# ProPrj_DCDC_LDO__2025-04-18.net
KiCad netlist of a schematic drawn in EasyEDA Pro
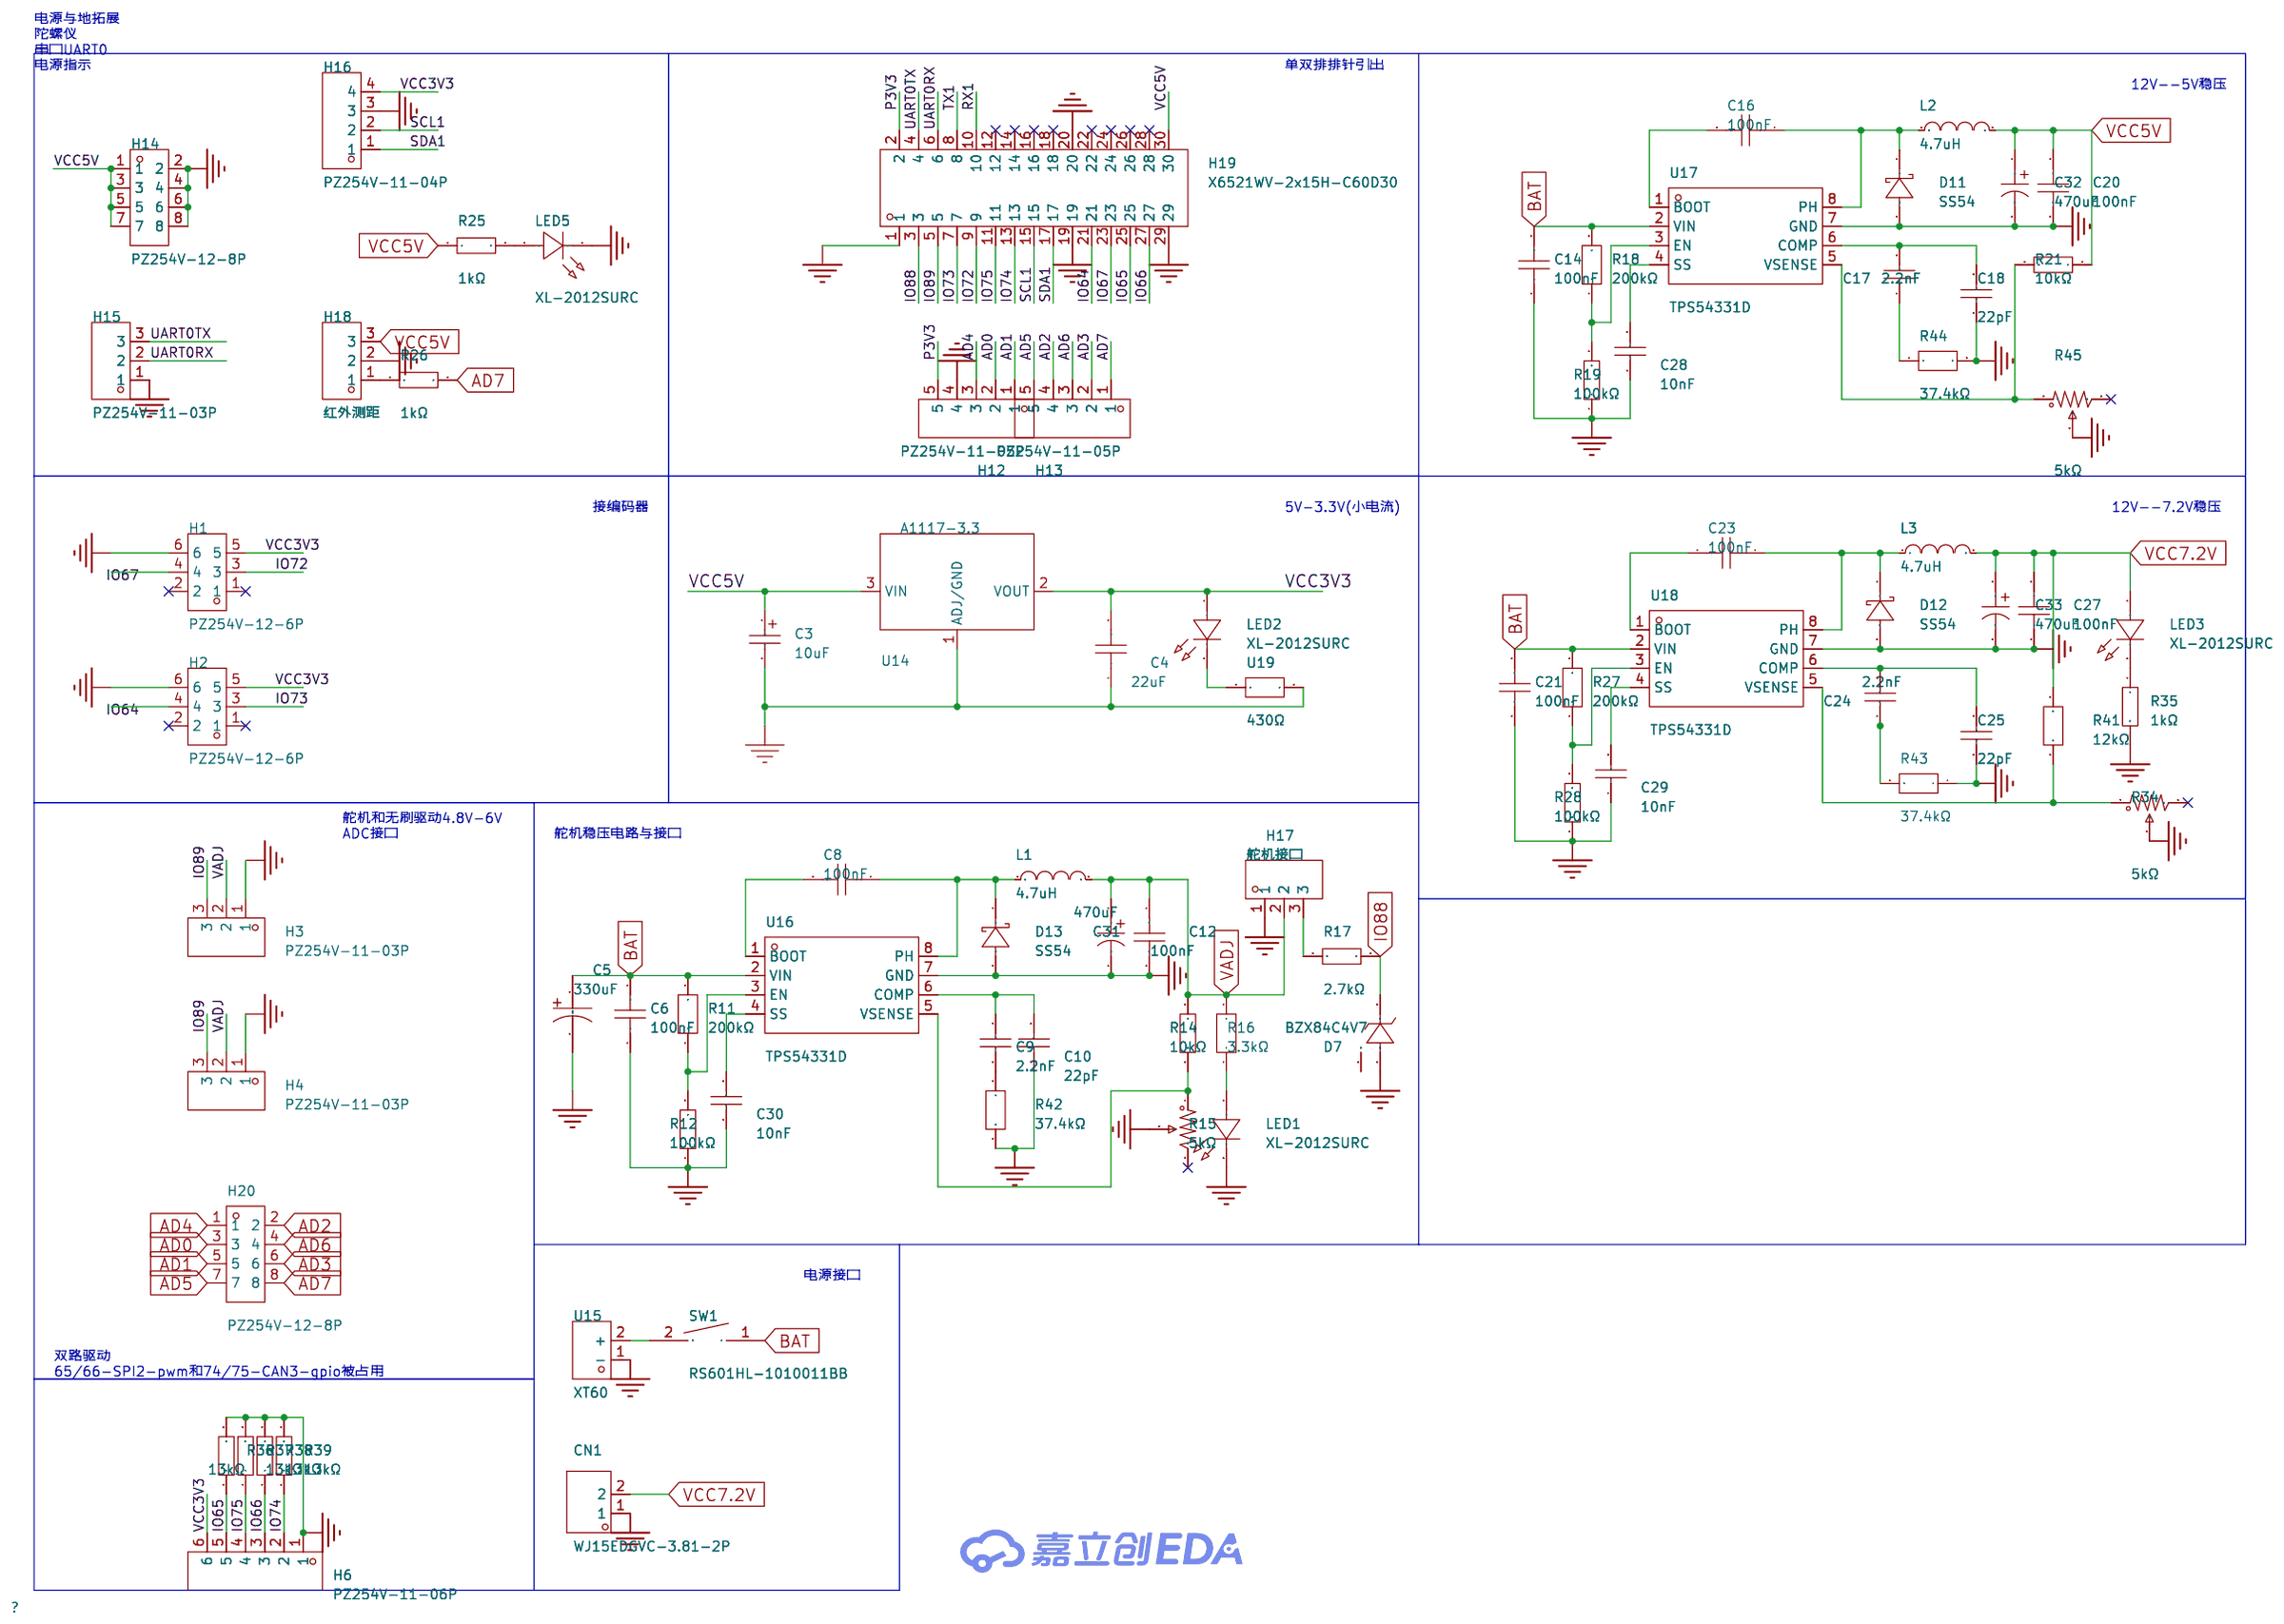
[diagram p0: schematic sheet]

(export (version "E")
  (design (tool "Eeschema 10.0.6"))
  (components
    (comp (ref "C3")
      (value "10uF")
      (footprint "easyedapro:CAP-SMD_L6.0-W3.2")
      (description "容值:10uF;精度:±10%;额定电压:16V;等效串联电阻:2Ω@100kHz;")
      (fields (field (name "Manufacturer Part") "TAJC106K016RNJ") (field (name "Manufacturer") "Kyocera AVX"))
      (libsource (lib "easyedapro") (part "TAJC106K016RNJ"))
    )
    (comp (ref "C4")
      (value "22uF")
      (footprint "easyedapro:C0805")
      (description "容值:22uF;精度:±20%;额定电压:35V;材质(温度系数):X5R;")
      (fields
        (field (name "Manufacturer Part") "CGA0805X5R226M350MT")
        (field (name "Manufacturer") "HRE(芯声)")
      )
      (libsource (lib "easyedapro") (part "CGA0805X5R226M350MT"))
    )
    (comp (ref "C5")
      (value "330uF")
      (footprint "easyedapro:CAP-SMD_BD8.0-L8.3-W8.3-LS9.3-FD-1")
      (description "容值:330uF;精度:±20%;额定电压:25V;纹波电流:228mA@120Hz;等效串联电阻(ESR):-;")
      (fields (field (name "Manufacturer Part") "RVT1E331M0810") (field (name "Manufacturer") "ROQANG(容强)"))
      (libsource (lib "easyedapro") (part "RVT1E331M0810_C335985"))
    )
    (comp (ref "C6")
      (value "100nF")
      (footprint "easyedapro:C0805")
      (description "容值:100nF;精度:±10%;额定电压:50V;材质(温度系数):X7R;")
      (fields
        (field (name "Manufacturer Part") "CC0805KRX7R9BB104")
        (field (name "Manufacturer") "YAGEO(国巨)")
      )
      (libsource (lib "easyedapro") (part "CC0805KRX7R9BB104"))
    )
    (comp (ref "C8")
      (value "100nF")
      (footprint "easyedapro:C0805")
      (description "容值:100nF;精度:±10%;额定电压:50V;材质(温度系数):X7R;")
      (fields
        (field (name "Manufacturer Part") "CC0805KRX7R9BB104")
        (field (name "Manufacturer") "YAGEO(国巨)")
      )
      (libsource (lib "easyedapro") (part "CC0805KRX7R9BB104"))
    )
    (comp (ref "C9")
      (value "2.2nF")
      (footprint "easyedapro:C0805")
      (description "容值:2.2nF;精度:±5%;额定电压:50V;材质(温度系数):C0G;")
      (fields
        (field (name "Manufacturer Part") "CL21C222JBFNNNE")
        (field (name "Manufacturer") "SAMSUNG(三星)")
      )
      (libsource (lib "easyedapro") (part "CL21C222JBFNNNE"))
    )
    (comp (ref "C10")
      (value "22pF")
      (footprint "easyedapro:C0603")
      (description "容值:22pF;精度:±5%;额定电压:50V;材质(温度系数):NP0;")
      (fields
        (field (name "Manufacturer Part") "CC0603JRNPO9BN220")
        (field (name "Manufacturer") "YAGEO(国巨)")
      )
      (libsource (lib "easyedapro") (part "CC0603JRNPO9BN220"))
    )
    (comp (ref "C12")
      (value "100nF")
      (footprint "easyedapro:C0805")
      (description "容值:100nF;精度:±10%;额定电压:50V;材质(温度系数):X7R;")
      (fields
        (field (name "Manufacturer Part") "CC0805KRX7R9BB104")
        (field (name "Manufacturer") "YAGEO(国巨)")
      )
      (libsource (lib "easyedapro") (part "CC0805KRX7R9BB104"))
    )
    (comp (ref "C14")
      (value "100nF")
      (footprint "easyedapro:C0805")
      (description "容值:100nF;精度:±10%;额定电压:50V;材质(温度系数):X7R;")
      (fields
        (field (name "Manufacturer Part") "CC0805KRX7R9BB104")
        (field (name "Manufacturer") "YAGEO(国巨)")
      )
      (libsource (lib "easyedapro") (part "CC0805KRX7R9BB104"))
    )
    (comp (ref "C16")
      (value "100nF")
      (footprint "easyedapro:C0805")
      (description "容值:100nF;精度:±10%;额定电压:50V;材质(温度系数):X7R;")
      (fields
        (field (name "Manufacturer Part") "CC0805KRX7R9BB104")
        (field (name "Manufacturer") "YAGEO(国巨)")
      )
      (libsource (lib "easyedapro") (part "CC0805KRX7R9BB104"))
    )
    (comp (ref "C17")
      (value "2.2nF")
      (footprint "easyedapro:C0805")
      (description "容值:2.2nF;精度:±5%;额定电压:50V;材质(温度系数):C0G;")
      (fields
        (field (name "Manufacturer Part") "CL21C222JBFNNNE")
        (field (name "Manufacturer") "SAMSUNG(三星)")
      )
      (libsource (lib "easyedapro") (part "CL21C222JBFNNNE"))
    )
    (comp (ref "C18")
      (value "22pF")
      (footprint "easyedapro:C0603")
      (description "容值:22pF;精度:±5%;额定电压:50V;材质(温度系数):NP0;")
      (fields
        (field (name "Manufacturer Part") "CC0603JRNPO9BN220")
        (field (name "Manufacturer") "YAGEO(国巨)")
      )
      (libsource (lib "easyedapro") (part "CC0603JRNPO9BN220"))
    )
    (comp (ref "C20")
      (value "100nF")
      (footprint "easyedapro:C0805")
      (description "容值:100nF;精度:±10%;额定电压:50V;材质(温度系数):X7R;")
      (fields
        (field (name "Manufacturer Part") "CC0805KRX7R9BB104")
        (field (name "Manufacturer") "YAGEO(国巨)")
      )
      (libsource (lib "easyedapro") (part "CC0805KRX7R9BB104"))
    )
    (comp (ref "C21")
      (value "100nF")
      (footprint "easyedapro:C0805")
      (description "容值:100nF;精度:±10%;额定电压:50V;材质(温度系数):X7R;")
      (fields
        (field (name "Manufacturer Part") "CC0805KRX7R9BB104")
        (field (name "Manufacturer") "YAGEO(国巨)")
      )
      (libsource (lib "easyedapro") (part "CC0805KRX7R9BB104"))
    )
    (comp (ref "C23")
      (value "100nF")
      (footprint "easyedapro:C0805")
      (description "容值:100nF;精度:±10%;额定电压:50V;材质(温度系数):X7R;")
      (fields
        (field (name "Manufacturer Part") "CC0805KRX7R9BB104")
        (field (name "Manufacturer") "YAGEO(国巨)")
      )
      (libsource (lib "easyedapro") (part "CC0805KRX7R9BB104"))
    )
    (comp (ref "C24")
      (value "2.2nF")
      (footprint "easyedapro:C0805")
      (description "容值:2.2nF;精度:±5%;额定电压:50V;材质(温度系数):C0G;")
      (fields
        (field (name "Manufacturer Part") "CL21C222JBFNNNE")
        (field (name "Manufacturer") "SAMSUNG(三星)")
      )
      (libsource (lib "easyedapro") (part "CL21C222JBFNNNE"))
    )
    (comp (ref "C25")
      (value "22pF")
      (footprint "easyedapro:C0603")
      (description "容值:22pF;精度:±5%;额定电压:50V;材质(温度系数):NP0;")
      (fields
        (field (name "Manufacturer Part") "CC0603JRNPO9BN220")
        (field (name "Manufacturer") "YAGEO(国巨)")
      )
      (libsource (lib "easyedapro") (part "CC0603JRNPO9BN220"))
    )
    (comp (ref "C27")
      (value "100nF")
      (footprint "easyedapro:C0805")
      (description "容值:100nF;精度:±10%;额定电压:50V;材质(温度系数):X7R;")
      (fields
        (field (name "Manufacturer Part") "CC0805KRX7R9BB104")
        (field (name "Manufacturer") "YAGEO(国巨)")
      )
      (libsource (lib "easyedapro") (part "CC0805KRX7R9BB104"))
    )
    (comp (ref "C28")
      (value "10nF")
      (footprint "easyedapro:C0805")
      (description "容值:10nF;精度:±10%;额定电压:50V;材质(温度系数):X7R;")
      (fields
        (field (name "Manufacturer Part") "CL21B103KBANNNC")
        (field (name "Manufacturer") "SAMSUNG(三星)")
      )
      (libsource (lib "easyedapro") (part "CL21B103KBANNNC"))
    )
    (comp (ref "C29")
      (value "10nF")
      (footprint "easyedapro:C0805")
      (description "容值:10nF;精度:±10%;额定电压:50V;材质(温度系数):X7R;")
      (fields
        (field (name "Manufacturer Part") "CL21B103KBANNNC")
        (field (name "Manufacturer") "SAMSUNG(三星)")
      )
      (libsource (lib "easyedapro") (part "CL21B103KBANNNC"))
    )
    (comp (ref "C30")
      (value "10nF")
      (footprint "easyedapro:C0805")
      (description "容值:10nF;精度:±10%;额定电压:50V;材质(温度系数):X7R;")
      (fields
        (field (name "Manufacturer Part") "CL21B103KBANNNC")
        (field (name "Manufacturer") "SAMSUNG(三星)")
      )
      (libsource (lib "easyedapro") (part "CL21B103KBANNNC"))
    )
    (comp (ref "C31")
      (value "470uF")
      (footprint "easyedapro:CAP-SMD_BD8.0-L8.3-W8.3-LS8.9-FD")
      (description "容值:470uF;精度:±20%;额定电压:16V;纹波电流:240mA@120Hz;")
      (fields (field (name "Manufacturer Part") "CK1C471M-CRF10") (field (name "Manufacturer") "ROQANG(容强)"))
      (libsource (lib "easyedapro") (part "CK1C471M-CRF10_C5162359"))
    )
    (comp (ref "C32")
      (value "470uF")
      (footprint "easyedapro:CAP-SMD_BD8.0-L8.3-W8.3-LS8.9-FD")
      (description "容值:470uF;精度:±20%;额定电压:16V;纹波电流:240mA@120Hz;")
      (fields (field (name "Manufacturer Part") "CK1C471M-CRF10") (field (name "Manufacturer") "ROQANG(容强)"))
      (libsource (lib "easyedapro") (part "CK1C471M-CRF10_C5162359"))
    )
    (comp (ref "C33")
      (value "470uF")
      (footprint "easyedapro:CAP-SMD_BD8.0-L8.3-W8.3-LS8.9-FD")
      (description "容值:470uF;精度:±20%;额定电压:16V;纹波电流:240mA@120Hz;")
      (fields (field (name "Manufacturer Part") "CK1C471M-CRF10") (field (name "Manufacturer") "ROQANG(容强)"))
      (libsource (lib "easyedapro") (part "CK1C471M-CRF10_C5162359"))
    )
    (comp (ref "CN1")
      (value "WJ15EDGVC-3.81-2P")
      (footprint "easyedapro:CONN-TH_WJ15EDGVC-3.81-2P")
      (fields (field (name "Manufacturer") "KANGNEX(康奈克斯电气)"))
      (libsource (lib "easyedapro") (part "WJ15EDGVC-3.81-2P"))
    )
    (comp (ref "D7")
      (value "BZX84C4V7")
      (footprint "easyedapro:SOT-23-3_L2.9-W1.3-P1.90-LS2.4-BR")
      (description "二极管配置:独立式;稳压值(标称值):4.7V;稳压值(范围):4.4V~5V;耗散功率(Pd):350mW;")
      (fields (field (name "Manufacturer") "LGE(鲁光)"))
      (libsource (lib "easyedapro") (part "BZX84C4V7_C841158"))
    )
    (comp (ref "D11")
      (value "SS54")
      (footprint "easyedapro:SMA_L4.3-W2.6-LS5.0-RD")
      (description "二极管配置:独立式;正向压降(Vf):550mV@5A;直流反向耐压(Vr):40V;整流电流:5A;")
      (fields (field (name "Manufacturer") "TWGMC(台湾迪嘉)"))
      (libsource (lib "easyedapro") (part "SS54_C727065"))
    )
    (comp (ref "D12")
      (value "SS54")
      (footprint "easyedapro:SMA_L4.3-W2.6-LS5.0-RD")
      (description "二极管配置:独立式;正向压降(Vf):550mV@5A;直流反向耐压(Vr):40V;整流电流:5A;")
      (fields (field (name "Manufacturer") "TWGMC(台湾迪嘉)"))
      (libsource (lib "easyedapro") (part "SS54_C727065"))
    )
    (comp (ref "D13")
      (value "SS54")
      (footprint "easyedapro:SMA_L4.3-W2.6-LS5.0-RD")
      (description "二极管配置:独立式;正向压降(Vf):550mV@5A;直流反向耐压(Vr):40V;整流电流:5A;")
      (fields (field (name "Manufacturer") "TWGMC(台湾迪嘉)"))
      (libsource (lib "easyedapro") (part "SS54_C727065"))
    )
    (comp (ref "H1")
      (value "PZ254V-12-6P")
      (footprint "easyedapro:HDR-TH_6P-P2.54-V-M-R2-C3-S2.54")
      (fields (field (name "Manufacturer") "XFCN(兴飞)"))
      (libsource (lib "easyedapro") (part "PZ254V-12-6P"))
    )
    (comp (ref "H2")
      (value "PZ254V-12-6P")
      (footprint "easyedapro:HDR-TH_6P-P2.54-V-M-R2-C3-S2.54")
      (fields (field (name "Manufacturer") "XFCN(兴飞)"))
      (libsource (lib "easyedapro") (part "PZ254V-12-6P"))
    )
    (comp (ref "H3")
      (value "PZ254V-11-03P")
      (footprint "easyedapro:HDR-TH_3P-P2.54-V-M")
      (fields (field (name "Manufacturer") "XFCN(兴飞)"))
      (libsource (lib "easyedapro") (part "PZ254V-11-03P_C2937625"))
    )
    (comp (ref "H4")
      (value "PZ254V-11-03P")
      (footprint "easyedapro:HDR-TH_3P-P2.54-V-M")
      (fields (field (name "Manufacturer") "XFCN(兴飞)"))
      (libsource (lib "easyedapro") (part "PZ254V-11-03P_C2937625"))
    )
    (comp (ref "H6")
      (value "PZ254V-11-06P")
      (footprint "easyedapro:HDR-TH_6P-P2.54-V-M")
      (fields (field (name "Manufacturer") "XFCN(兴飞)"))
      (libsource (lib "easyedapro") (part "PZ254V-11-06P"))
    )
    (comp (ref "H12")
      (value "PZ254V-11-05P")
      (footprint "easyedapro:HDR-TH_5P-P2.54-V-M")
      (fields (field (name "Manufacturer") "XFCN(兴飞)"))
      (libsource (lib "easyedapro") (part "PZ254V-11-05P"))
    )
    (comp (ref "H13")
      (value "PZ254V-11-05P")
      (footprint "easyedapro:HDR-TH_5P-P2.54-V-M")
      (fields (field (name "Manufacturer") "XFCN(兴飞)"))
      (libsource (lib "easyedapro") (part "PZ254V-11-05P"))
    )
    (comp (ref "H14")
      (value "PZ254V-12-8P")
      (footprint "easyedapro:HDR-TH_8P-P2.54-V-M-R2-C4-S2.54")
      (fields (field (name "Manufacturer") "XFCN(兴飞)"))
      (libsource (lib "easyedapro") (part "PZ254V-12-8P"))
    )
    (comp (ref "H15")
      (value "PZ254V-11-03P")
      (footprint "easyedapro:HDR-TH_3P-P2.54-V-M")
      (fields (field (name "Manufacturer") "XFCN(兴飞)"))
      (libsource (lib "easyedapro") (part "PZ254V-11-03P_C2937625"))
    )
    (comp (ref "H16")
      (value "PZ254V-11-04P")
      (footprint "easyedapro:HDR-TH_4P-P2.54-V-M")
      (fields (field (name "Manufacturer") "XFCN(兴飞)"))
      (libsource (lib "easyedapro") (part "PZ254V-11-04P_C2691448"))
    )
    (comp (ref "H17")
      (value "舵机接口")
      (footprint "easyedapro:HDR-TH_3P-P2.54-V-M")
      (fields (field (name "Manufacturer") "XFCN(兴飞)"))
      (libsource (lib "easyedapro") (part "PZ254V-11-03P_C2937625"))
    )
    (comp (ref "H18")
      (value "红外测距")
      (footprint "easyedapro:HDR-TH_3P-P2.54-V-M")
      (fields (field (name "Manufacturer") "XFCN(兴飞)"))
      (libsource (lib "easyedapro") (part "PZ254V-11-03P_C2937625"))
    )
    (comp (ref "H19")
      (value "X6521WV-2x15H-C60D30")
      (footprint "easyedapro:HDR-TH_30P-P2.54-V-M-R2-C15-S2.54-BL")
      (fields (field (name "Manufacturer") "XKB Connection(中国星坤)"))
      (libsource (lib "easyedapro") (part "X6521WV-2×15H-C30D60"))
    )
    (comp (ref "H20")
      (value "PZ254V-12-8P")
      (footprint "easyedapro:HDR-TH_8P-P2.54-V-M-R2-C4-S2.54")
      (fields (field (name "Manufacturer") "XFCN(兴飞)"))
      (libsource (lib "easyedapro") (part "PZ254V-12-8P"))
    )
    (comp (ref "L1")
      (value "4.7uH")
      (footprint "easyedapro:IND-SMD_L7.3-W6.6_MHCI06030")
      (description "电感值:4.7uH;精度:±20%;额定电流:5.5A;")
      (fields
        (field (name "Manufacturer Part") "SLO0630H4R7MTT")
        (field (name "Manufacturer") "Sunltech(韩国顺磁)")
      )
      (libsource (lib "easyedapro") (part "SLO0630H4R7MTT"))
    )
    (comp (ref "L2")
      (value "4.7uH")
      (footprint "easyedapro:IND-SMD_L7.3-W6.6_MHCI06030")
      (description "电感值:4.7uH;精度:±20%;额定电流:5.5A;")
      (fields
        (field (name "Manufacturer Part") "SLO0630H4R7MTT")
        (field (name "Manufacturer") "Sunltech(韩国顺磁)")
      )
      (libsource (lib "easyedapro") (part "SLO0630H4R7MTT"))
    )
    (comp (ref "L3")
      (value "4.7uH")
      (footprint "easyedapro:IND-SMD_L7.3-W6.6_MHCI06030")
      (description "电感值:4.7uH;精度:±20%;额定电流:5.5A;")
      (fields
        (field (name "Manufacturer Part") "SLO0630H4R7MTT")
        (field (name "Manufacturer") "Sunltech(韩国顺磁)")
      )
      (libsource (lib "easyedapro") (part "SLO0630H4R7MTT"))
    )
    (comp (ref "LED1")
      (value "XL-2012SURC")
      (footprint "easyedapro:LED0805-R-RD")
      (description "发光颜色:红色;功率:55mW;正向电流:25mA;主波长:617nm~621nm;透镜颜色:无色透明透镜;色温:-;发光角度:120°;载带方式:正贴;工作温度:-30°C~+85°C;")
      (fields (field (name "Manufacturer") "XINGLIGHT(成兴光)"))
      (libsource (lib "easyedapro") (part "XL-2012SURC"))
    )
    (comp (ref "LED2")
      (value "XL-2012SURC")
      (footprint "easyedapro:LED0805-R-RD")
      (description "发光颜色:红色;功率:55mW;正向电流:25mA;主波长:617nm~621nm;透镜颜色:无色透明透镜;色温:-;发光角度:120°;载带方式:正贴;工作温度:-30°C~+85°C;")
      (fields (field (name "Manufacturer") "XINGLIGHT(成兴光)"))
      (libsource (lib "easyedapro") (part "XL-2012SURC"))
    )
    (comp (ref "LED3")
      (value "XL-2012SURC")
      (footprint "easyedapro:LED0805-R-RD")
      (description "发光颜色:红色;功率:55mW;正向电流:25mA;主波长:617nm~621nm;透镜颜色:无色透明透镜;色温:-;发光角度:120°;载带方式:正贴;工作温度:-30°C~+85°C;")
      (fields (field (name "Manufacturer") "XINGLIGHT(成兴光)"))
      (libsource (lib "easyedapro") (part "XL-2012SURC"))
    )
    (comp (ref "LED5")
      (value "XL-2012SURC")
      (footprint "easyedapro:LED0805-R-RD")
      (description "发光颜色:红色;功率:55mW;正向电流:25mA;主波长:617nm~621nm;透镜颜色:无色透明透镜;色温:-;发光角度:120°;载带方式:正贴;工作温度:-30°C~+85°C;")
      (fields (field (name "Manufacturer") "XINGLIGHT(成兴光)"))
      (libsource (lib "easyedapro") (part "XL-2012SURC"))
    )
    (comp (ref "R11")
      (value "200kΩ")
      (footprint "easyedapro:R0603")
      (description "电阻类型:厚膜电阻;阻值:200kΩ;精度:±1%;功率:100mW;工作电压:75V;温度系数:±100ppm/°C;")
      (fields (field (name "Manufacturer Part") "FRC0603F2003TS") (field (name "Manufacturer") "FOJAN(富捷)"))
      (libsource (lib "easyedapro") (part "FRC0603F2003TS"))
    )
    (comp (ref "R12")
      (value "100kΩ")
      (footprint "easyedapro:R0805")
      (description "电阻类型:厚膜电阻;阻值:100kΩ;精度:±1%;功率:125mW;最大工作电压:150V;温度系数:±100ppm/°C;")
      (fields
        (field (name "Manufacturer Part") "0805W8F1003T5E")
        (field (name "Manufacturer") "UNI-ROYAL(厚声)")
      )
      (libsource (lib "easyedapro") (part "0805W8F1003T5E_C149504"))
    )
    (comp (ref "R14")
      (value "10kΩ")
      (footprint "easyedapro:R0805")
      (description "电阻类型:厚膜电阻;阻值:10kΩ;精度:±1%;功率:125mW;最大工作电压:150V;温度系数:±100ppm/°C;")
      (fields
        (field (name "Manufacturer Part") "0805W8F1002T5E")
        (field (name "Manufacturer") "UNI-ROYAL(厚声)")
      )
      (libsource (lib "easyedapro") (part "0805W8F1002T5E"))
    )
    (comp (ref "R15")
      (value "5kΩ")
      (footprint "easyedapro:RES-ADJ-TH_3P-L6.8-W4.6-P2.50-TL-BS-3266X")
      (description "阻值:5kΩ;精度:±10%;功率:250mW;温度系数:±100ppm/°C;")
      (fields (field (name "Manufacturer Part") "3266X-1-502LF") (field (name "Manufacturer") "BOURNS"))
      (libsource (lib "easyedapro") (part "3266X-1-502LF"))
    )
    (comp (ref "R16")
      (value "3.3kΩ")
      (footprint "easyedapro:R0805")
      (description "电阻类型:厚膜电阻;阻值:3.3kΩ;精度:±1%;功率:125mW;最大工作电压:150V;温度系数:±100ppm/°C;")
      (fields (field (name "Manufacturer Part") "FRC0805F3301TS") (field (name "Manufacturer") "FOJAN(富捷)"))
      (libsource (lib "easyedapro") (part "FRC0805F3301TS"))
    )
    (comp (ref "R17")
      (value "2.7kΩ")
      (footprint "easyedapro:R0603")
      (description "电阻类型:厚膜电阻;阻值:2.7kΩ;精度:±1%;功率:100mW;最大工作电压:75V;温度系数:±100ppm/°C;")
      (fields
        (field (name "Manufacturer Part") "0603WAF2701T5E")
        (field (name "Manufacturer") "UNI-ROYAL(厚声)")
      )
      (libsource (lib "easyedapro") (part "0603WAF2701T5E"))
    )
    (comp (ref "R18")
      (value "200kΩ")
      (footprint "easyedapro:R0603")
      (description "电阻类型:厚膜电阻;阻值:200kΩ;精度:±1%;功率:100mW;工作电压:75V;温度系数:±100ppm/°C;")
      (fields (field (name "Manufacturer Part") "FRC0603F2003TS") (field (name "Manufacturer") "FOJAN(富捷)"))
      (libsource (lib "easyedapro") (part "FRC0603F2003TS"))
    )
    (comp (ref "R19")
      (value "100kΩ")
      (footprint "easyedapro:R0805")
      (description "电阻类型:厚膜电阻;阻值:100kΩ;精度:±1%;功率:125mW;最大工作电压:150V;温度系数:±100ppm/°C;")
      (fields
        (field (name "Manufacturer Part") "0805W8F1003T5E")
        (field (name "Manufacturer") "UNI-ROYAL(厚声)")
      )
      (libsource (lib "easyedapro") (part "0805W8F1003T5E_C149504"))
    )
    (comp (ref "R21")
      (value "10kΩ")
      (footprint "easyedapro:R0805")
      (description "电阻类型:厚膜电阻;阻值:10kΩ;精度:±1%;功率:125mW;最大工作电压:150V;温度系数:±100ppm/°C;")
      (fields
        (field (name "Manufacturer Part") "0805W8F1002T5E")
        (field (name "Manufacturer") "UNI-ROYAL(厚声)")
      )
      (libsource (lib "easyedapro") (part "0805W8F1002T5E"))
    )
    (comp (ref "R25")
      (value "1kΩ")
      (footprint "easyedapro:R0603")
      (description "电阻类型:厚膜电阻;阻值:1kΩ;精度:±1%;功率:100mW;最大工作电压:75V;温度系数:±100ppm/°C;")
      (fields
        (field (name "Manufacturer Part") "0603WAF1001T5E")
        (field (name "Manufacturer") "UNI-ROYAL(厚声)")
      )
      (libsource (lib "easyedapro") (part "0603WAF1001T5E"))
    )
    (comp (ref "R26")
      (value "1kΩ")
      (footprint "easyedapro:R0603")
      (description "电阻类型:厚膜电阻;阻值:1kΩ;精度:±1%;功率:100mW;最大工作电压:75V;温度系数:±100ppm/°C;")
      (fields
        (field (name "Manufacturer Part") "0603WAF1001T5E")
        (field (name "Manufacturer") "UNI-ROYAL(厚声)")
      )
      (libsource (lib "easyedapro") (part "0603WAF1001T5E"))
    )
    (comp (ref "R27")
      (value "200kΩ")
      (footprint "easyedapro:R0603")
      (description "电阻类型:厚膜电阻;阻值:200kΩ;精度:±1%;功率:100mW;工作电压:75V;温度系数:±100ppm/°C;")
      (fields (field (name "Manufacturer Part") "FRC0603F2003TS") (field (name "Manufacturer") "FOJAN(富捷)"))
      (libsource (lib "easyedapro") (part "FRC0603F2003TS"))
    )
    (comp (ref "R28")
      (value "100kΩ")
      (footprint "easyedapro:R0805")
      (description "电阻类型:厚膜电阻;阻值:100kΩ;精度:±1%;功率:125mW;最大工作电压:150V;温度系数:±100ppm/°C;")
      (fields
        (field (name "Manufacturer Part") "0805W8F1003T5E")
        (field (name "Manufacturer") "UNI-ROYAL(厚声)")
      )
      (libsource (lib "easyedapro") (part "0805W8F1003T5E_C149504"))
    )
    (comp (ref "R34")
      (value "5kΩ")
      (footprint "easyedapro:RES-ADJ-TH_3P-L6.8-W4.6-P2.50-TL-BS-3266X")
      (description "阻值:5kΩ;精度:±10%;功率:250mW;温度系数:±100ppm/°C;")
      (fields (field (name "Manufacturer Part") "3266X-1-502LF") (field (name "Manufacturer") "BOURNS"))
      (libsource (lib "easyedapro") (part "3266X-1-502LF"))
    )
    (comp (ref "R35")
      (value "1kΩ")
      (footprint "easyedapro:R0603")
      (description "电阻类型:厚膜电阻;阻值:510Ω;精度:±1%;功率:100mW;最大工作电压:75V;温度系数:±100ppm/°C;")
      (fields
        (field (name "Manufacturer Part") "0603WAF5100T5E")
        (field (name "Manufacturer") "UNI-ROYAL(厚声)")
      )
      (libsource (lib "easyedapro") (part "0603WAF5100T5E"))
    )
    (comp (ref "R36")
      (value "13kΩ")
      (footprint "easyedapro:R0805")
      (description "电阻类型:厚膜电阻;阻值:13kΩ;精度:±1%;功率:125mW;最大工作电压:150V;温度系数:±100ppm/°C;")
      (fields
        (field (name "Manufacturer Part") "0805W8F1302T5E")
        (field (name "Manufacturer") "UNI-ROYAL(厚声)")
      )
      (libsource (lib "easyedapro") (part "0805W8F1302T5E"))
    )
    (comp (ref "R37")
      (value "13kΩ")
      (footprint "easyedapro:R0805")
      (description "电阻类型:厚膜电阻;阻值:13kΩ;精度:±1%;功率:125mW;最大工作电压:150V;温度系数:±100ppm/°C;")
      (fields
        (field (name "Manufacturer Part") "0805W8F1302T5E")
        (field (name "Manufacturer") "UNI-ROYAL(厚声)")
      )
      (libsource (lib "easyedapro") (part "0805W8F1302T5E"))
    )
    (comp (ref "R38")
      (value "13kΩ")
      (footprint "easyedapro:R0805")
      (description "电阻类型:厚膜电阻;阻值:13kΩ;精度:±1%;功率:125mW;最大工作电压:150V;温度系数:±100ppm/°C;")
      (fields
        (field (name "Manufacturer Part") "0805W8F1302T5E")
        (field (name "Manufacturer") "UNI-ROYAL(厚声)")
      )
      (libsource (lib "easyedapro") (part "0805W8F1302T5E"))
    )
    (comp (ref "R39")
      (value "13kΩ")
      (footprint "easyedapro:R0805")
      (description "电阻类型:厚膜电阻;阻值:13kΩ;精度:±1%;功率:125mW;最大工作电压:150V;温度系数:±100ppm/°C;")
      (fields
        (field (name "Manufacturer Part") "0805W8F1302T5E")
        (field (name "Manufacturer") "UNI-ROYAL(厚声)")
      )
      (libsource (lib "easyedapro") (part "0805W8F1302T5E"))
    )
    (comp (ref "R41")
      (value "12kΩ")
      (footprint "easyedapro:R0805")
      (description "电阻类型:厚膜电阻;阻值:12kΩ;精度:±1%;功率:125mW;最大工作电压:150V;温度系数:±100ppm/°C;")
      (fields (field (name "Manufacturer Part") "FRC0805F1202TS") (field (name "Manufacturer") "FOJAN(富捷)"))
      (libsource (lib "easyedapro") (part "FRC0805F1202TS"))
    )
    (comp (ref "R42")
      (value "37.4kΩ")
      (footprint "easyedapro:R0603")
      (description "电阻类型:薄膜电阻;阻值:37kΩ;精度:±0.25%;功率:100mW;最大工作电压:75V;温度系数:±25ppm/°C;")
      (fields (field (name "Manufacturer Part") "RN73R1JTTD3702C25") (field (name "Manufacturer") "KOA"))
      (libsource (lib "easyedapro") (part "RN73R1JTTD3702C25"))
    )
    (comp (ref "R43")
      (value "37.4kΩ")
      (footprint "easyedapro:R0603")
      (description "电阻类型:薄膜电阻;阻值:37kΩ;精度:±0.25%;功率:100mW;最大工作电压:75V;温度系数:±25ppm/°C;")
      (fields (field (name "Manufacturer Part") "RN73R1JTTD3702C25") (field (name "Manufacturer") "KOA"))
      (libsource (lib "easyedapro") (part "RN73R1JTTD3702C25"))
    )
    (comp (ref "R44")
      (value "37.4kΩ")
      (footprint "easyedapro:R0603")
      (description "电阻类型:薄膜电阻;阻值:37kΩ;精度:±0.25%;功率:100mW;最大工作电压:75V;温度系数:±25ppm/°C;")
      (fields (field (name "Manufacturer Part") "RN73R1JTTD3702C25") (field (name "Manufacturer") "KOA"))
      (libsource (lib "easyedapro") (part "RN73R1JTTD3702C25"))
    )
    (comp (ref "R45")
      (value "5kΩ")
      (footprint "easyedapro:RES-ADJ-TH_3P-L6.8-W4.6-P2.50-TL-BS-3266X")
      (description "阻值:5kΩ;精度:±10%;功率:250mW;温度系数:±100ppm/°C;")
      (fields (field (name "Manufacturer Part") "3266X-1-502LF") (field (name "Manufacturer") "BOURNS"))
      (libsource (lib "easyedapro") (part "3266X-1-502LF"))
    )
    (comp (ref "SW1")
      (value "RS601HL-1010011BB")
      (footprint "easyedapro:SW-TH_RS601HL-1010011BB")
      (description "带灯:无;引脚样式:焊片;额定电流:3A;额定电压(AC):250V;额定电压(DC):-;电路结构:单刀单掷;机械寿命:1万次;")
      (fields (field (name "Manufacturer") "HCTL(华灿天禄)"))
      (libsource (lib "easyedapro") (part "RS601HL-1010011BB"))
    )
    (comp (ref "U14")
      (value "A1117-3.3")
      (footprint "easyedapro:asm1117")
      (fields (field (name "Manufacturer") "IDCHIP(英锐芯)"))
      (libsource (lib "easyedapro") (part "A1117-3.3"))
    )
    (comp (ref "U15")
      (value "XT60")
      (footprint "easyedapro:CONN-TH_XT60")
      (description "类别:-;类型1:-;")
      (fields (field (name "Manufacturer") "AMASS(艾迈斯)"))
      (libsource (lib "easyedapro") (part "XT60"))
    )
    (comp (ref "U16")
      (value "TPS54331D")
      (footprint "easyedapro:SOIC-8_L4.9-W3.9-P1.27-LS6.0-BL")
      (description "功能类型:降压型;输出类型:可调;输入电压:3.5V~28V;输出电压:-;输出电流:3A;")
      (fields (field (name "Manufacturer") "TI(德州仪器)"))
      (libsource (lib "easyedapro") (part "TPS54331D"))
    )
    (comp (ref "U17")
      (value "TPS54331D")
      (footprint "easyedapro:SOIC-8_L4.9-W3.9-P1.27-LS6.0-BL")
      (description "功能类型:降压型;输出类型:可调;输入电压:3.5V~28V;输出电压:-;输出电流:3A;")
      (fields (field (name "Manufacturer") "TI(德州仪器)"))
      (libsource (lib "easyedapro") (part "TPS54331D"))
    )
    (comp (ref "U18")
      (value "TPS54331D")
      (footprint "easyedapro:SOIC-8_L4.9-W3.9-P1.27-LS6.0-BL")
      (description "功能类型:降压型;输出类型:可调;输入电压:3.5V~28V;输出电压:-;输出电流:3A;")
      (fields (field (name "Manufacturer") "TI(德州仪器)"))
      (libsource (lib "easyedapro") (part "TPS54331D"))
    )
    (comp (ref "U19")
      (value "430Ω")
      (footprint "easyedapro:R0805")
      (description "电阻类型:厚膜电阻;阻值:430Ω;精度:±1%;功率:125mW;最大工作电压:150V;温度系数:±100ppm/°C;")
      (fields (field (name "Manufacturer Part") "FRC0805F4300TS") (field (name "Manufacturer") "FOJAN(富捷)"))
      (libsource (lib "easyedapro") (part "FRC0805F4300TS"))
    )
  )
  (nets
    (net (code "1") (name "/IO64") (class "Default")
      (node (ref "H19") (pin "21") (pinfunction "21_21") (pintype "unspecified"))
      (node (ref "H2") (pin "4") (pinfunction "4_4") (pintype "unspecified"))
    )
    (net (code "2") (name "/IO65") (class "Default")
      (node (ref "H19") (pin "25") (pinfunction "25_25") (pintype "unspecified"))
      (node (ref "H6") (pin "5") (pinfunction "5_5") (pintype "unspecified"))
      (node (ref "R36") (pin "1") (pinfunction "1_1") (pintype "input"))
    )
    (net (code "3") (name "/IO66") (class "Default")
      (node (ref "H19") (pin "27") (pinfunction "27_27") (pintype "unspecified"))
      (node (ref "H6") (pin "3") (pinfunction "3_3") (pintype "unspecified"))
      (node (ref "R38") (pin "1") (pinfunction "1_1") (pintype "input"))
    )
    (net (code "4") (name "/IO67") (class "Default")
      (node (ref "H1") (pin "4") (pinfunction "4_4") (pintype "unspecified"))
      (node (ref "H19") (pin "23") (pinfunction "23_23") (pintype "unspecified"))
    )
    (net (code "5") (name "/IO72") (class "Default")
      (node (ref "H1") (pin "3") (pinfunction "3_3") (pintype "unspecified"))
      (node (ref "H19") (pin "9") (pinfunction "9_9") (pintype "unspecified"))
    )
    (net (code "6") (name "/IO73") (class "Default")
      (node (ref "H19") (pin "7") (pinfunction "7_7") (pintype "unspecified"))
      (node (ref "H2") (pin "3") (pinfunction "3_3") (pintype "unspecified"))
    )
    (net (code "7") (name "/IO74") (class "Default")
      (node (ref "H19") (pin "13") (pinfunction "13_13") (pintype "unspecified"))
      (node (ref "H6") (pin "2") (pinfunction "2_2") (pintype "unspecified"))
      (node (ref "R39") (pin "1") (pinfunction "1_1") (pintype "input"))
    )
    (net (code "8") (name "/IO75") (class "Default")
      (node (ref "H19") (pin "11") (pinfunction "11_11") (pintype "unspecified"))
      (node (ref "H6") (pin "4") (pinfunction "4_4") (pintype "unspecified"))
      (node (ref "R37") (pin "1") (pinfunction "1_1") (pintype "input"))
    )
    (net (code "9") (name "/IO89") (class "Default")
      (node (ref "H19") (pin "5") (pinfunction "5_5") (pintype "unspecified"))
      (node (ref "H3") (pin "3") (pinfunction "3_3") (pintype "unspecified"))
      (node (ref "H4") (pin "3") (pinfunction "3_3") (pintype "unspecified"))
    )
    (net (code "10") (name "/P3V3") (class "Default")
      (node (ref "H12") (pin "5") (pinfunction "5_5") (pintype "unspecified"))
      (node (ref "H19") (pin "2") (pinfunction "2_2") (pintype "unspecified"))
    )
    (net (code "11") (name "/RX1") (class "Default")
      (node (ref "H19") (pin "10") (pinfunction "10_10") (pintype "unspecified"))
    )
    (net (code "12") (name "/SCL1") (class "Default")
      (node (ref "H16") (pin "2") (pinfunction "2_2") (pintype "unspecified"))
      (node (ref "H19") (pin "15") (pinfunction "15_15") (pintype "unspecified"))
    )
    (net (code "13") (name "/SDA1") (class "Default")
      (node (ref "H16") (pin "1") (pinfunction "1_1") (pintype "unspecified"))
      (node (ref "H19") (pin "17") (pinfunction "17_17") (pintype "unspecified"))
    )
    (net (code "14") (name "/TX1") (class "Default")
      (node (ref "H19") (pin "8") (pinfunction "8_8") (pintype "unspecified"))
    )
    (net (code "15") (name "/UART0RX") (class "Default")
      (node (ref "H15") (pin "2") (pinfunction "2_2") (pintype "unspecified"))
      (node (ref "H19") (pin "6") (pinfunction "6_6") (pintype "unspecified"))
    )
    (net (code "16") (name "/UART0TX") (class "Default")
      (node (ref "H15") (pin "3") (pinfunction "3_3") (pintype "unspecified"))
      (node (ref "H19") (pin "4") (pinfunction "4_4") (pintype "unspecified"))
    )
    (net (code "17") (name "/VCC3V3") (class "Default")
      (node (ref "C4") (pin "2") (pinfunction "2_2") (pintype "unspecified"))
      (node (ref "H1") (pin "5") (pinfunction "5_5") (pintype "unspecified"))
      (node (ref "H16") (pin "4") (pinfunction "4_4") (pintype "unspecified"))
      (node (ref "H2") (pin "5") (pinfunction "5_5") (pintype "unspecified"))
      (node (ref "H6") (pin "6") (pinfunction "6_6") (pintype "unspecified"))
      (node (ref "LED2") (pin "1") (pinfunction "A_1") (pintype "unspecified"))
      (node (ref "U14") (pin "2") (pinfunction "VOUT_2") (pintype "input"))
    )
    (net (code "18") (name "AD0") (class "Default")
      (node (ref "H12") (pin "2") (pinfunction "2_2") (pintype "unspecified"))
      (node (ref "H20") (pin "3") (pinfunction "3_3") (pintype "unspecified"))
    )
    (net (code "19") (name "AD1") (class "Default")
      (node (ref "H12") (pin "1") (pinfunction "1_1") (pintype "unspecified"))
      (node (ref "H20") (pin "5") (pinfunction "5_5") (pintype "unspecified"))
    )
    (net (code "20") (name "AD2") (class "Default")
      (node (ref "H13") (pin "4") (pinfunction "4_4") (pintype "unspecified"))
      (node (ref "H20") (pin "2") (pinfunction "2_2") (pintype "unspecified"))
    )
    (net (code "21") (name "AD3") (class "Default")
      (node (ref "H13") (pin "2") (pinfunction "2_2") (pintype "unspecified"))
      (node (ref "H20") (pin "6") (pinfunction "6_6") (pintype "unspecified"))
    )
    (net (code "22") (name "AD4") (class "Default")
      (node (ref "H12") (pin "3") (pinfunction "3_3") (pintype "unspecified"))
      (node (ref "H20") (pin "1") (pinfunction "1_1") (pintype "unspecified"))
    )
    (net (code "23") (name "AD5") (class "Default")
      (node (ref "H13") (pin "5") (pinfunction "5_5") (pintype "unspecified"))
      (node (ref "H20") (pin "7") (pinfunction "7_7") (pintype "unspecified"))
    )
    (net (code "24") (name "AD6") (class "Default")
      (node (ref "H13") (pin "3") (pinfunction "3_3") (pintype "unspecified"))
      (node (ref "H20") (pin "4") (pinfunction "4_4") (pintype "unspecified"))
    )
    (net (code "25") (name "AD7") (class "Default")
      (node (ref "H13") (pin "1") (pinfunction "1_1") (pintype "unspecified"))
      (node (ref "H20") (pin "8") (pinfunction "8_8") (pintype "unspecified"))
      (node (ref "R26") (pin "2") (pinfunction "2_2") (pintype "input"))
    )
    (net (code "26") (name "BAT") (class "Default")
      (node (ref "C14") (pin "2") (pinfunction "2_2") (pintype "unspecified"))
      (node (ref "C21") (pin "2") (pinfunction "2_2") (pintype "unspecified"))
      (node (ref "C5") (pin "1") (pinfunction "1_1") (pintype "unspecified"))
      (node (ref "C6") (pin "2") (pinfunction "2_2") (pintype "unspecified"))
      (node (ref "R11") (pin "2") (pinfunction "2_2") (pintype "unspecified"))
      (node (ref "R18") (pin "2") (pinfunction "2_2") (pintype "unspecified"))
      (node (ref "R27") (pin "2") (pinfunction "2_2") (pintype "unspecified"))
      (node (ref "SW1") (pin "1") (pinfunction "1_1") (pintype "input"))
      (node (ref "U16") (pin "2") (pinfunction "VIN_2") (pintype "unspecified"))
      (node (ref "U17") (pin "2") (pinfunction "VIN_2") (pintype "unspecified"))
      (node (ref "U18") (pin "2") (pinfunction "VIN_2") (pintype "unspecified"))
    )
    (net (code "27") (name "GND") (class "Default")
      (node (ref "C10") (pin "1") (pinfunction "1_1") (pintype "input"))
      (node (ref "C12") (pin "2") (pinfunction "2_2") (pintype "unspecified"))
      (node (ref "C14") (pin "1") (pinfunction "1_1") (pintype "unspecified"))
      (node (ref "C18") (pin "1") (pinfunction "1_1") (pintype "input"))
      (node (ref "C20") (pin "2") (pinfunction "2_2") (pintype "unspecified"))
      (node (ref "C21") (pin "1") (pinfunction "1_1") (pintype "unspecified"))
      (node (ref "C25") (pin "1") (pinfunction "1_1") (pintype "input"))
      (node (ref "C27") (pin "2") (pinfunction "2_2") (pintype "unspecified"))
      (node (ref "C28") (pin "1") (pinfunction "1_1") (pintype "input"))
      (node (ref "C29") (pin "1") (pinfunction "1_1") (pintype "input"))
      (node (ref "C3") (pin "2") (pinfunction "2_2") (pintype "input"))
      (node (ref "C30") (pin "1") (pinfunction "1_1") (pintype "input"))
      (node (ref "C31") (pin "2") (pinfunction "2_2") (pintype "input"))
      (node (ref "C32") (pin "2") (pinfunction "2_2") (pintype "input"))
      (node (ref "C33") (pin "2") (pinfunction "2_2") (pintype "input"))
      (node (ref "C4") (pin "1") (pinfunction "1_1") (pintype "unspecified"))
      (node (ref "C5") (pin "2") (pinfunction "2_2") (pintype "unspecified"))
      (node (ref "C6") (pin "1") (pinfunction "1_1") (pintype "unspecified"))
      (node (ref "CN1") (pin "1") (pinfunction "1_1") (pintype "unspecified"))
      (node (ref "D11") (pin "2") (pinfunction "2_2") (pintype "unspecified"))
      (node (ref "D12") (pin "2") (pinfunction "2_2") (pintype "unspecified"))
      (node (ref "D13") (pin "2") (pinfunction "2_2") (pintype "unspecified"))
      (node (ref "D7") (pin "1") (pinfunction "A_1") (pintype "unspecified"))
      (node (ref "H1") (pin "6") (pinfunction "6_6") (pintype "unspecified"))
      (node (ref "H12") (pin "4") (pinfunction "4_4") (pintype "unspecified"))
      (node (ref "H14") (pin "2") (pinfunction "2_2") (pintype "unspecified"))
      (node (ref "H14") (pin "4") (pinfunction "4_4") (pintype "unspecified"))
      (node (ref "H14") (pin "6") (pinfunction "6_6") (pintype "unspecified"))
      (node (ref "H14") (pin "8") (pinfunction "8_8") (pintype "unspecified"))
      (node (ref "H15") (pin "1") (pinfunction "1_1") (pintype "unspecified"))
      (node (ref "H16") (pin "3") (pinfunction "3_3") (pintype "unspecified"))
      (node (ref "H17") (pin "1") (pinfunction "1_1") (pintype "unspecified"))
      (node (ref "H18") (pin "2") (pinfunction "2_2") (pintype "unspecified"))
      (node (ref "H19") (pin "1") (pinfunction "1_1") (pintype "unspecified"))
      (node (ref "H19") (pin "19") (pinfunction "19_19") (pintype "unspecified"))
      (node (ref "H19") (pin "20") (pinfunction "20_20") (pintype "unspecified"))
      (node (ref "H19") (pin "29") (pinfunction "29_29") (pintype "unspecified"))
      (node (ref "H2") (pin "6") (pinfunction "6_6") (pintype "unspecified"))
      (node (ref "H3") (pin "1") (pinfunction "1_1") (pintype "unspecified"))
      (node (ref "H4") (pin "1") (pinfunction "1_1") (pintype "unspecified"))
      (node (ref "H6") (pin "1") (pinfunction "1_1") (pintype "unspecified"))
      (node (ref "LED1") (pin "2") (pinfunction "K_2") (pintype "unspecified"))
      (node (ref "LED5") (pin "2") (pinfunction "K_2") (pintype "unspecified"))
      (node (ref "R12") (pin "1") (pinfunction "1_1") (pintype "unspecified"))
      (node (ref "R15") (pin "2") (pinfunction "2_2") (pintype "unspecified"))
      (node (ref "R19") (pin "1") (pinfunction "1_1") (pintype "unspecified"))
      (node (ref "R28") (pin "1") (pinfunction "1_1") (pintype "unspecified"))
      (node (ref "R34") (pin "2") (pinfunction "2_2") (pintype "unspecified"))
      (node (ref "R35") (pin "2") (pinfunction "2_2") (pintype "input"))
      (node (ref "R36") (pin "2") (pinfunction "2_2") (pintype "input"))
      (node (ref "R37") (pin "2") (pinfunction "2_2") (pintype "input"))
      (node (ref "R38") (pin "2") (pinfunction "2_2") (pintype "input"))
      (node (ref "R39") (pin "2") (pinfunction "2_2") (pintype "input"))
      (node (ref "R42") (pin "1") (pinfunction "1_1") (pintype "unspecified"))
      (node (ref "R43") (pin "1") (pinfunction "1_1") (pintype "unspecified"))
      (node (ref "R44") (pin "2") (pinfunction "2_2") (pintype "unspecified"))
      (node (ref "R45") (pin "2") (pinfunction "2_2") (pintype "unspecified"))
      (node (ref "U14") (pin "1") (pinfunction "ADJ/GND_1") (pintype "input"))
      (node (ref "U15") (pin "1") (pinfunction "-_1") (pintype "unspecified"))
      (node (ref "U16") (pin "7") (pinfunction "GND_7") (pintype "unspecified"))
      (node (ref "U17") (pin "7") (pinfunction "GND_7") (pintype "unspecified"))
      (node (ref "U18") (pin "7") (pinfunction "GND_7") (pintype "unspecified"))
      (node (ref "U19") (pin "2") (pinfunction "2_2") (pintype "unspecified"))
    )
    (net (code "28") (name "IO88") (class "Default")
      (node (ref "D7") (pin "3") (pinfunction "C_3") (pintype "unspecified"))
      (node (ref "H19") (pin "3") (pinfunction "3_3") (pintype "unspecified"))
      (node (ref "R17") (pin "1") (pinfunction "1_1") (pintype "input"))
    )
    (net (code "29") (name "Net-(C9-Pad1)") (class "Default")
      (node (ref "C9") (pin "1") (pinfunction "1_1") (pintype "input"))
      (node (ref "R42") (pin "2") (pinfunction "2_2") (pintype "unspecified"))
    )
    (net (code "30") (name "Net-(C17-Pad1)") (class "Default")
      (node (ref "C17") (pin "1") (pinfunction "1_1") (pintype "input"))
      (node (ref "R44") (pin "1") (pinfunction "1_1") (pintype "unspecified"))
    )
    (net (code "31") (name "Net-(C24-Pad1)") (class "Default")
      (node (ref "C24") (pin "1") (pinfunction "1_1") (pintype "input"))
      (node (ref "R43") (pin "2") (pinfunction "2_2") (pintype "unspecified"))
    )
    (net (code "32") (name "Net-(H17-Pad3)") (class "Default")
      (node (ref "H17") (pin "3") (pinfunction "3_3") (pintype "unspecified"))
      (node (ref "R17") (pin "2") (pinfunction "2_2") (pintype "input"))
    )
    (net (code "33") (name "Net-(H18-Pad1)") (class "Default")
      (node (ref "H18") (pin "1") (pinfunction "1_1") (pintype "unspecified"))
      (node (ref "R26") (pin "1") (pinfunction "1_1") (pintype "input"))
    )
    (net (code "34") (name "Net-(LED1-A)") (class "Default")
      (node (ref "LED1") (pin "1") (pinfunction "A_1") (pintype "unspecified"))
      (node (ref "R16") (pin "1") (pinfunction "1_1") (pintype "unspecified"))
    )
    (net (code "35") (name "Net-(LED2-K)") (class "Default")
      (node (ref "LED2") (pin "2") (pinfunction "K_2") (pintype "unspecified"))
      (node (ref "U19") (pin "1") (pinfunction "1_1") (pintype "unspecified"))
    )
    (net (code "36") (name "Net-(LED3-K)") (class "Default")
      (node (ref "LED3") (pin "2") (pinfunction "K_2") (pintype "unspecified"))
      (node (ref "R35") (pin "1") (pinfunction "1_1") (pintype "input"))
    )
    (net (code "37") (name "Net-(LED5-A)") (class "Default")
      (node (ref "LED5") (pin "1") (pinfunction "A_1") (pintype "unspecified"))
      (node (ref "R25") (pin "2") (pinfunction "2_2") (pintype "input"))
    )
    (net (code "38") (name "Net-(U15-+)") (class "Default")
      (node (ref "SW1") (pin "2") (pinfunction "2_2") (pintype "input"))
      (node (ref "U15") (pin "2") (pinfunction "+_2") (pintype "unspecified"))
    )
    (net (code "39") (name "Net-(U16-BOOT)") (class "Default")
      (node (ref "C8") (pin "2") (pinfunction "2_2") (pintype "unspecified"))
      (node (ref "U16") (pin "1") (pinfunction "BOOT_1") (pintype "unspecified"))
    )
    (net (code "40") (name "Net-(U16-COMP)") (class "Default")
      (node (ref "C10") (pin "2") (pinfunction "2_2") (pintype "input"))
      (node (ref "C9") (pin "2") (pinfunction "2_2") (pintype "input"))
      (node (ref "U16") (pin "6") (pinfunction "COMP_6") (pintype "unspecified"))
    )
    (net (code "41") (name "Net-(U16-EN)") (class "Default")
      (node (ref "R11") (pin "1") (pinfunction "1_1") (pintype "unspecified"))
      (node (ref "R12") (pin "2") (pinfunction "2_2") (pintype "unspecified"))
      (node (ref "U16") (pin "3") (pinfunction "EN_3") (pintype "unspecified"))
    )
    (net (code "42") (name "Net-(U16-PH)") (class "Default")
      (node (ref "C8") (pin "1") (pinfunction "1_1") (pintype "unspecified"))
      (node (ref "D13") (pin "1") (pinfunction "1_1") (pintype "unspecified"))
      (node (ref "L1") (pin "1") (pinfunction "1_1") (pintype "unspecified"))
      (node (ref "U16") (pin "8") (pinfunction "PH_8") (pintype "unspecified"))
    )
    (net (code "43") (name "Net-(U16-SS)") (class "Default")
      (node (ref "C30") (pin "2") (pinfunction "2_2") (pintype "input"))
      (node (ref "U16") (pin "4") (pinfunction "SS_4") (pintype "unspecified"))
    )
    (net (code "44") (name "Net-(U16-VSENSE)") (class "Default")
      (node (ref "R14") (pin "1") (pinfunction "1_1") (pintype "input"))
      (node (ref "R15") (pin "1") (pinfunction "1_1") (pintype "unspecified"))
      (node (ref "U16") (pin "5") (pinfunction "VSENSE_5") (pintype "unspecified"))
    )
    (net (code "45") (name "Net-(U17-BOOT)") (class "Default")
      (node (ref "C16") (pin "2") (pinfunction "2_2") (pintype "unspecified"))
      (node (ref "U17") (pin "1") (pinfunction "BOOT_1") (pintype "unspecified"))
    )
    (net (code "46") (name "Net-(U17-COMP)") (class "Default")
      (node (ref "C17") (pin "2") (pinfunction "2_2") (pintype "input"))
      (node (ref "C18") (pin "2") (pinfunction "2_2") (pintype "input"))
      (node (ref "U17") (pin "6") (pinfunction "COMP_6") (pintype "unspecified"))
    )
    (net (code "47") (name "Net-(U17-EN)") (class "Default")
      (node (ref "R18") (pin "1") (pinfunction "1_1") (pintype "unspecified"))
      (node (ref "R19") (pin "2") (pinfunction "2_2") (pintype "unspecified"))
      (node (ref "U17") (pin "3") (pinfunction "EN_3") (pintype "unspecified"))
    )
    (net (code "48") (name "Net-(U17-PH)") (class "Default")
      (node (ref "C16") (pin "1") (pinfunction "1_1") (pintype "unspecified"))
      (node (ref "D11") (pin "1") (pinfunction "1_1") (pintype "unspecified"))
      (node (ref "L2") (pin "1") (pinfunction "1_1") (pintype "unspecified"))
      (node (ref "U17") (pin "8") (pinfunction "PH_8") (pintype "unspecified"))
    )
    (net (code "49") (name "Net-(U17-SS)") (class "Default")
      (node (ref "C28") (pin "2") (pinfunction "2_2") (pintype "input"))
      (node (ref "U17") (pin "4") (pinfunction "SS_4") (pintype "unspecified"))
    )
    (net (code "50") (name "Net-(U17-VSENSE)") (class "Default")
      (node (ref "R21") (pin "2") (pinfunction "2_2") (pintype "input"))
      (node (ref "R45") (pin "1") (pinfunction "1_1") (pintype "unspecified"))
      (node (ref "U17") (pin "5") (pinfunction "VSENSE_5") (pintype "unspecified"))
    )
    (net (code "51") (name "Net-(U18-BOOT)") (class "Default")
      (node (ref "C23") (pin "2") (pinfunction "2_2") (pintype "unspecified"))
      (node (ref "U18") (pin "1") (pinfunction "BOOT_1") (pintype "unspecified"))
    )
    (net (code "52") (name "Net-(U18-COMP)") (class "Default")
      (node (ref "C24") (pin "2") (pinfunction "2_2") (pintype "input"))
      (node (ref "C25") (pin "2") (pinfunction "2_2") (pintype "input"))
      (node (ref "U18") (pin "6") (pinfunction "COMP_6") (pintype "unspecified"))
    )
    (net (code "53") (name "Net-(U18-EN)") (class "Default")
      (node (ref "R27") (pin "1") (pinfunction "1_1") (pintype "unspecified"))
      (node (ref "R28") (pin "2") (pinfunction "2_2") (pintype "unspecified"))
      (node (ref "U18") (pin "3") (pinfunction "EN_3") (pintype "unspecified"))
    )
    (net (code "54") (name "Net-(U18-PH)") (class "Default")
      (node (ref "C23") (pin "1") (pinfunction "1_1") (pintype "unspecified"))
      (node (ref "D12") (pin "1") (pinfunction "1_1") (pintype "unspecified"))
      (node (ref "L3") (pin "1") (pinfunction "1_1") (pintype "unspecified"))
      (node (ref "U18") (pin "8") (pinfunction "PH_8") (pintype "unspecified"))
    )
    (net (code "55") (name "Net-(U18-SS)") (class "Default")
      (node (ref "C29") (pin "2") (pinfunction "2_2") (pintype "input"))
      (node (ref "U18") (pin "4") (pinfunction "SS_4") (pintype "unspecified"))
    )
    (net (code "56") (name "Net-(U18-VSENSE)") (class "Default")
      (node (ref "R34") (pin "1") (pinfunction "1_1") (pintype "unspecified"))
      (node (ref "R41") (pin "1") (pinfunction "1_1") (pintype "unspecified"))
      (node (ref "U18") (pin "5") (pinfunction "VSENSE_5") (pintype "unspecified"))
    )
    (net (code "57") (name "VADJ") (class "Default")
      (node (ref "C12") (pin "1") (pinfunction "1_1") (pintype "unspecified"))
      (node (ref "C31") (pin "1") (pinfunction "1_1") (pintype "input"))
      (node (ref "H17") (pin "2") (pinfunction "2_2") (pintype "unspecified"))
      (node (ref "H3") (pin "2") (pinfunction "2_2") (pintype "unspecified"))
      (node (ref "H4") (pin "2") (pinfunction "2_2") (pintype "unspecified"))
      (node (ref "L1") (pin "2") (pinfunction "2_2") (pintype "unspecified"))
      (node (ref "R14") (pin "2") (pinfunction "2_2") (pintype "input"))
      (node (ref "R16") (pin "2") (pinfunction "2_2") (pintype "unspecified"))
    )
    (net (code "58") (name "VCC5V") (class "Default")
      (node (ref "C20") (pin "1") (pinfunction "1_1") (pintype "unspecified"))
      (node (ref "C3") (pin "1") (pinfunction "1_1") (pintype "input"))
      (node (ref "C32") (pin "1") (pinfunction "1_1") (pintype "input"))
      (node (ref "H14") (pin "1") (pinfunction "1_1") (pintype "unspecified"))
      (node (ref "H14") (pin "3") (pinfunction "3_3") (pintype "unspecified"))
      (node (ref "H14") (pin "5") (pinfunction "5_5") (pintype "unspecified"))
      (node (ref "H14") (pin "7") (pinfunction "7_7") (pintype "unspecified"))
      (node (ref "H18") (pin "3") (pinfunction "3_3") (pintype "unspecified"))
      (node (ref "H19") (pin "30") (pinfunction "30_30") (pintype "unspecified"))
      (node (ref "L2") (pin "2") (pinfunction "2_2") (pintype "unspecified"))
      (node (ref "R21") (pin "1") (pinfunction "1_1") (pintype "input"))
      (node (ref "R25") (pin "1") (pinfunction "1_1") (pintype "input"))
      (node (ref "U14") (pin "3") (pinfunction "VIN_3") (pintype "input"))
    )
    (net (code "59") (name "VCC7.2V") (class "Default")
      (node (ref "C27") (pin "1") (pinfunction "1_1") (pintype "unspecified"))
      (node (ref "C33") (pin "1") (pinfunction "1_1") (pintype "input"))
      (node (ref "CN1") (pin "2") (pinfunction "2_2") (pintype "unspecified"))
      (node (ref "L3") (pin "2") (pinfunction "2_2") (pintype "unspecified"))
      (node (ref "LED3") (pin "1") (pinfunction "A_1") (pintype "unspecified"))
      (node (ref "R41") (pin "2") (pinfunction "2_2") (pintype "unspecified"))
    )
    (net (code "60") (name "unconnected-(D7-NC-Pad2)") (class "Default")
      (node (ref "D7") (pin "2") (pinfunction "NC_2") (pintype "unspecified"))
    )
    (net (code "61") (name "unconnected-(H1-Pad1)") (class "Default")
      (node (ref "H1") (pin "1") (pinfunction "1_1") (pintype "unspecified+no_connect"))
    )
    (net (code "62") (name "unconnected-(H1-Pad2)") (class "Default")
      (node (ref "H1") (pin "2") (pinfunction "2_2") (pintype "unspecified+no_connect"))
    )
    (net (code "63") (name "unconnected-(H2-Pad1)") (class "Default")
      (node (ref "H2") (pin "1") (pinfunction "1_1") (pintype "unspecified+no_connect"))
    )
    (net (code "64") (name "unconnected-(H2-Pad2)") (class "Default")
      (node (ref "H2") (pin "2") (pinfunction "2_2") (pintype "unspecified+no_connect"))
    )
    (net (code "65") (name "unconnected-(H19-Pad12)") (class "Default")
      (node (ref "H19") (pin "12") (pinfunction "12_12") (pintype "unspecified+no_connect"))
    )
    (net (code "66") (name "unconnected-(H19-Pad14)") (class "Default")
      (node (ref "H19") (pin "14") (pinfunction "14_14") (pintype "unspecified+no_connect"))
    )
    (net (code "67") (name "unconnected-(H19-Pad16)") (class "Default")
      (node (ref "H19") (pin "16") (pinfunction "16_16") (pintype "unspecified+no_connect"))
    )
    (net (code "68") (name "unconnected-(H19-Pad18)") (class "Default")
      (node (ref "H19") (pin "18") (pinfunction "18_18") (pintype "unspecified+no_connect"))
    )
    (net (code "69") (name "unconnected-(H19-Pad22)") (class "Default")
      (node (ref "H19") (pin "22") (pinfunction "22_22") (pintype "unspecified+no_connect"))
    )
    (net (code "70") (name "unconnected-(H19-Pad24)") (class "Default")
      (node (ref "H19") (pin "24") (pinfunction "24_24") (pintype "unspecified+no_connect"))
    )
    (net (code "71") (name "unconnected-(H19-Pad26)") (class "Default")
      (node (ref "H19") (pin "26") (pinfunction "26_26") (pintype "unspecified+no_connect"))
    )
    (net (code "72") (name "unconnected-(H19-Pad28)") (class "Default")
      (node (ref "H19") (pin "28") (pinfunction "28_28") (pintype "unspecified+no_connect"))
    )
    (net (code "73") (name "unconnected-(R15-Pad3)") (class "Default")
      (node (ref "R15") (pin "3") (pinfunction "3_3") (pintype "unspecified+no_connect"))
    )
    (net (code "74") (name "unconnected-(R34-Pad3)") (class "Default")
      (node (ref "R34") (pin "3") (pinfunction "3_3") (pintype "unspecified+no_connect"))
    )
    (net (code "75") (name "unconnected-(R45-Pad3)") (class "Default")
      (node (ref "R45") (pin "3") (pinfunction "3_3") (pintype "unspecified+no_connect"))
    )
  )
)
